# SmartThermo1_4.net
KiCad netlist of a schematic drawn in EAGLE
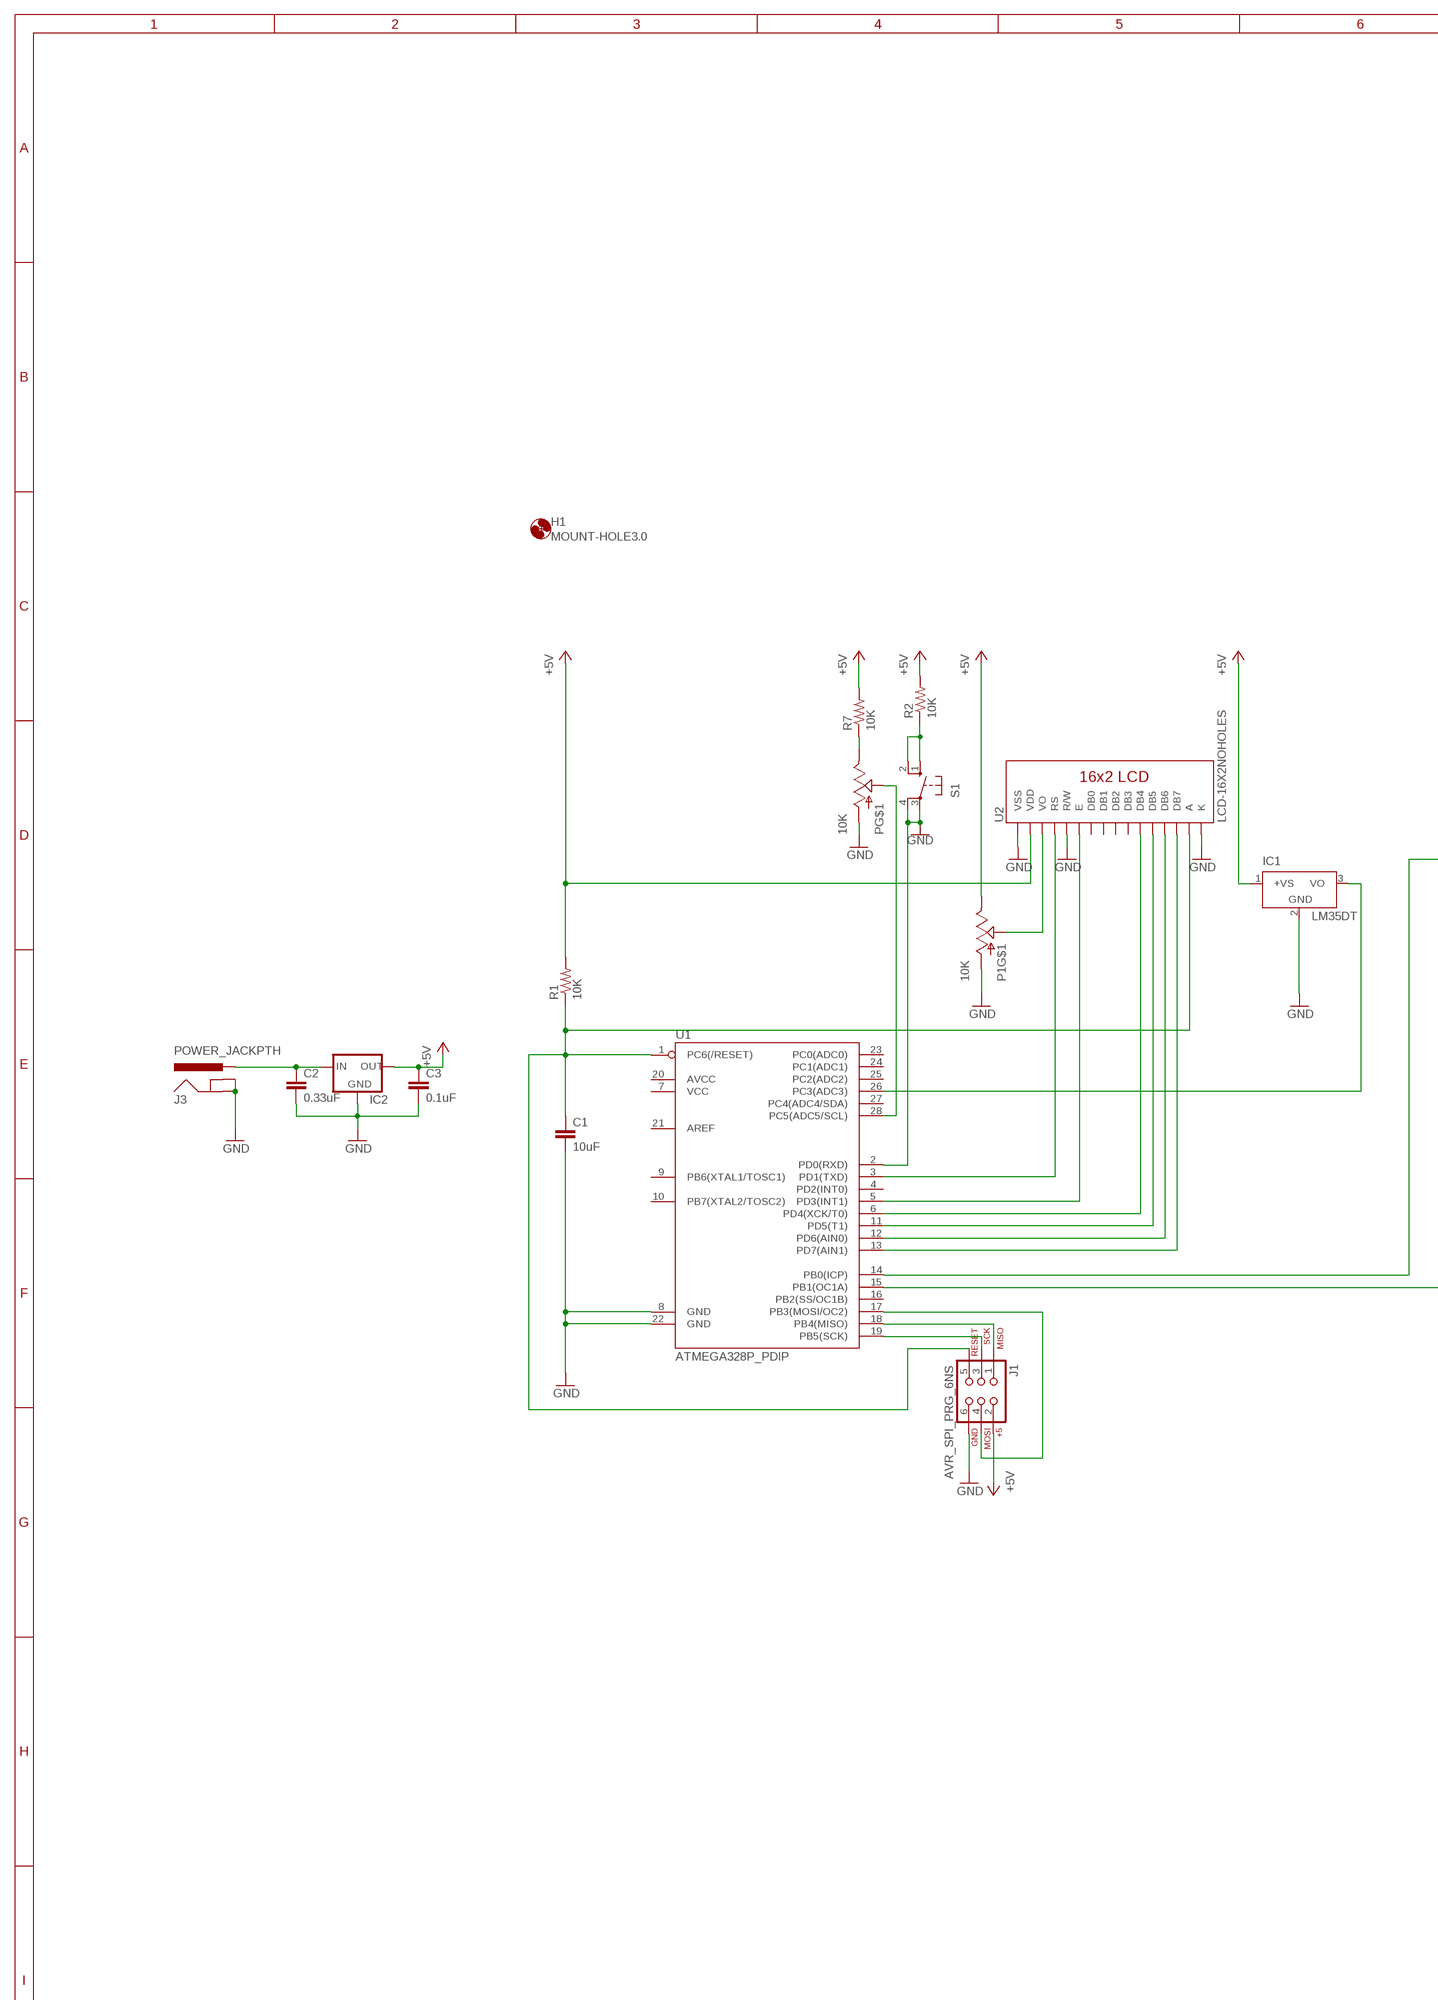
[diagram p0: schematic, sheet 1, part 1 of 2]
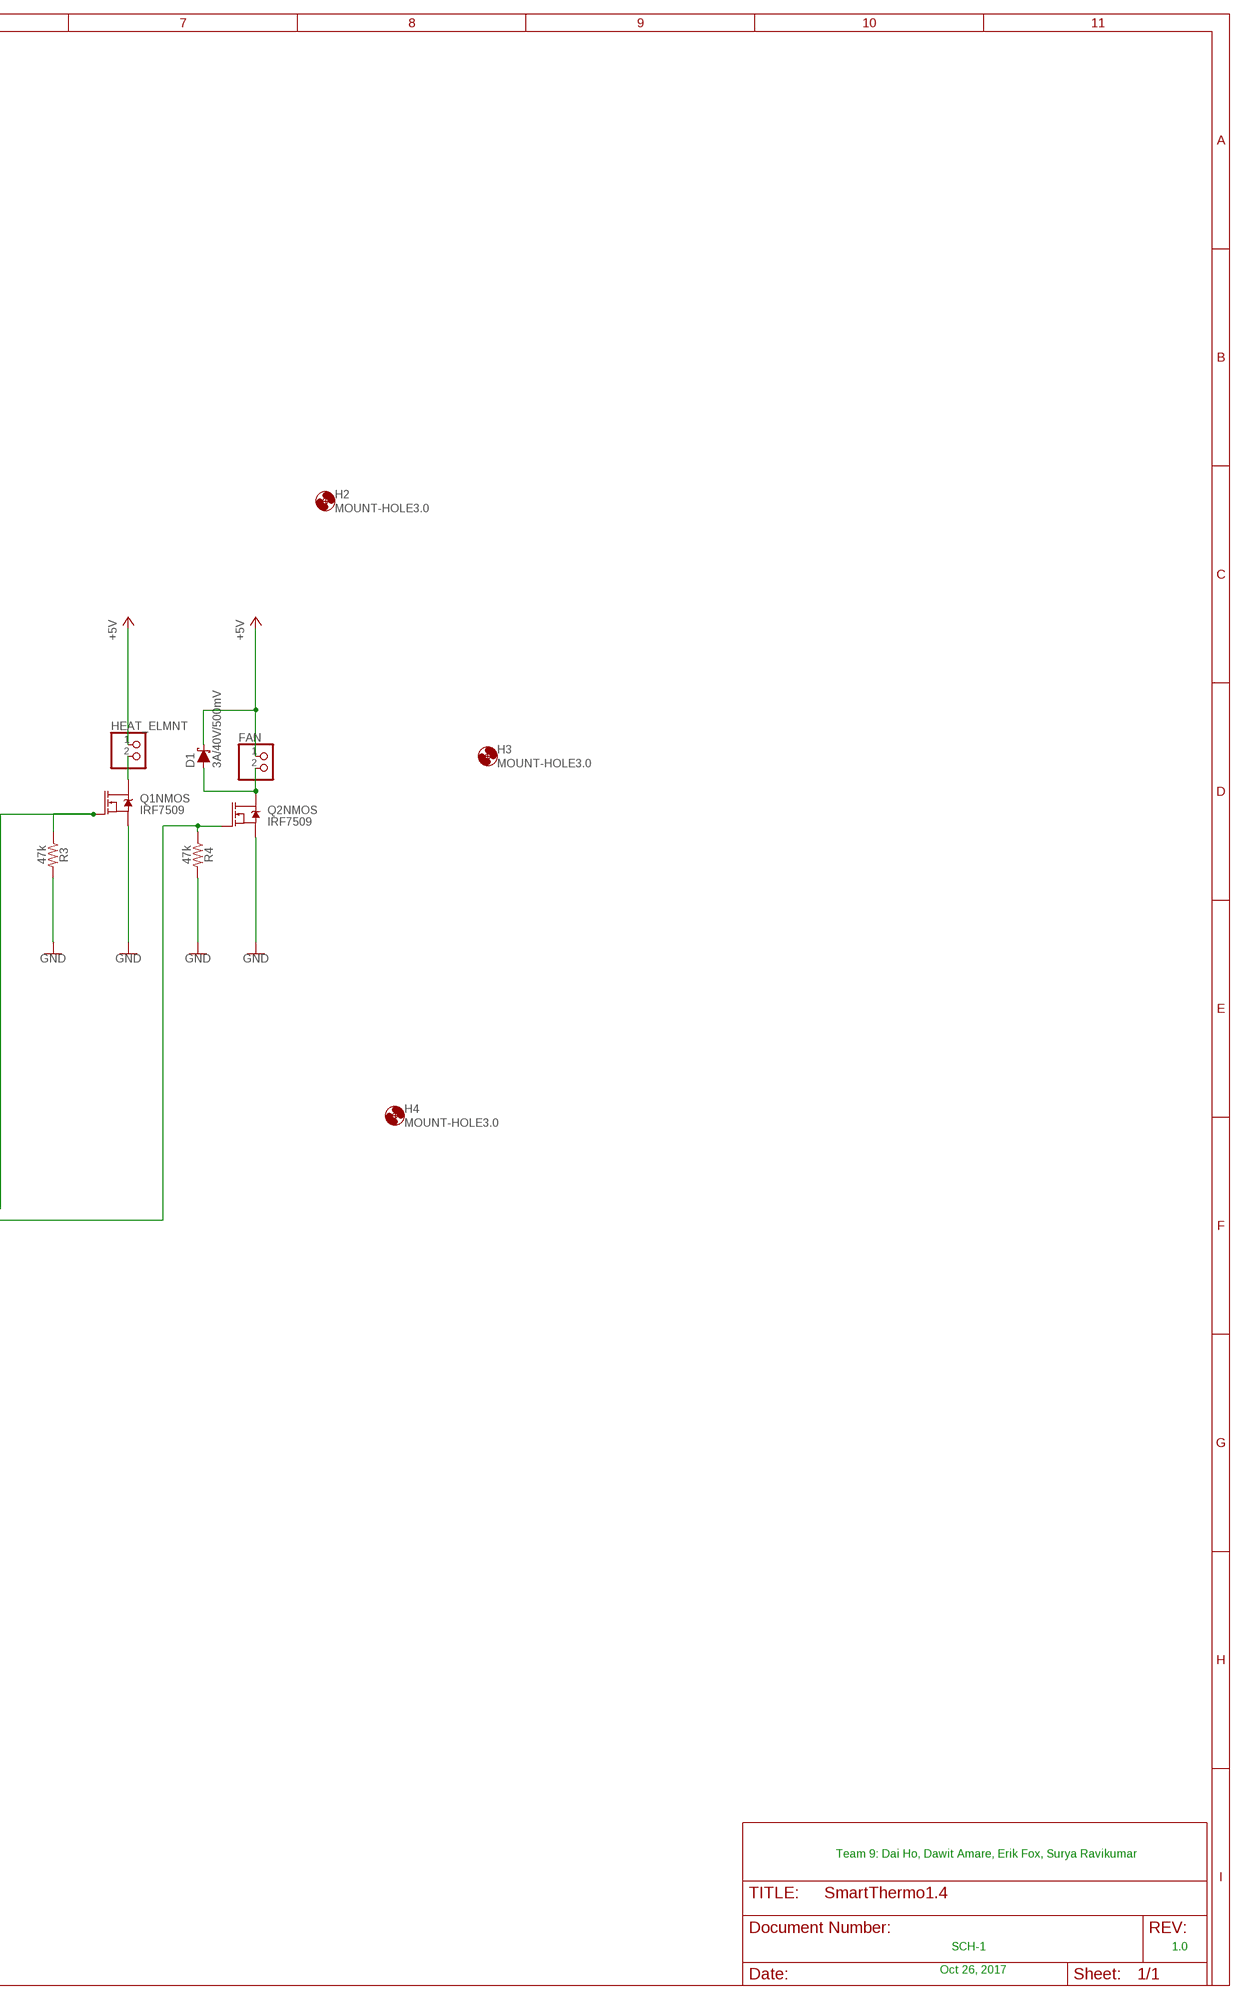
[diagram p1: schematic, sheet 1, part 2 of 2]

(export (version "E")
  (design (tool "Eeschema 10.0.6"))
  (components
    (comp (ref "C1")
      (value "10uF")
      (footprint "eagle-import:1206")
      (libsource (lib "eagle-import") (part "10UF-6.3V-20%(1206)"))
    )
    (comp (ref "C2")
      (value "0.33uF")
      (footprint "eagle-import:C7.5B3")
      (libsource (lib "eagle-import") (part "C7.5/3"))
    )
    (comp (ref "C3")
      (value "0.1uF")
      (footprint "eagle-import:C7.5B3")
      (libsource (lib "eagle-import") (part "C7.5/3"))
    )
    (comp (ref "D1")
      (value "3A/40V/500mV")
      (footprint "eagle-import:SMA-DIODE")
      (libsource (lib "eagle-import") (part "DIODE-SCHOTTKY-B340A"))
    )
    (comp (ref "FAN")
      (value "PINHD-1X2/90")
      (footprint "eagle-import:1X02_90")
      (libsource (lib "eagle-import") (part "PINHD-1X2/90"))
    )
    (comp (ref "H1")
      (value "MOUNT-HOLE3.0")
      (footprint "eagle-import:3,0")
      (libsource (lib "eagle-import") (part "MOUNT-HOLE3.0"))
    )
    (comp (ref "H2")
      (value "MOUNT-HOLE3.0")
      (footprint "eagle-import:3,0")
      (libsource (lib "eagle-import") (part "MOUNT-HOLE3.0"))
    )
    (comp (ref "H3")
      (value "MOUNT-HOLE3.0")
      (footprint "eagle-import:3,0")
      (libsource (lib "eagle-import") (part "MOUNT-HOLE3.0"))
    )
    (comp (ref "H4")
      (value "MOUNT-HOLE3.0")
      (footprint "eagle-import:3,0")
      (libsource (lib "eagle-import") (part "MOUNT-HOLE3.0"))
    )
    (comp (ref "HEAT_ELMNT")
      (value "PINHD-1X2/90")
      (footprint "eagle-import:1X02_90")
      (libsource (lib "eagle-import") (part "PINHD-1X2/90"))
    )
    (comp (ref "IC1")
      (value "LM35DT")
      (footprint "eagle-import:TO220V")
      (libsource (lib "eagle-import") (part "LM35DT"))
    )
    (comp (ref "IC2")
      (value "78XXL")
      (footprint "eagle-import:78XXL")
      (libsource (lib "eagle-import") (part "78XXL"))
    )
    (comp (ref "J1")
      (value "AVR_SPI_PRG_6NS")
      (footprint "eagle-import:2X3-NS")
      (libsource (lib "eagle-import") (part "AVR_SPI_PRG_6NS"))
    )
    (comp (ref "J3")
      (value "POWER_JACKPTH")
      (footprint "eagle-import:POWER_JACK_PTH")
      (libsource (lib "eagle-import") (part "POWER_JACKPTH"))
    )
    (comp (ref "P")
      (value "10K")
      (footprint "eagle-import:POT_PTH")
      (libsource (lib "eagle-import") (part "POT_SWITCHPOT_PTH"))
    )
    (comp (ref "P1")
      (value "10K")
      (footprint "eagle-import:POT_PTH")
      (libsource (lib "eagle-import") (part "POT_SWITCHPOT_PTH"))
    )
    (comp (ref "Q1")
      (value "IRF7509")
      (footprint "eagle-import:MSOP8")
      (libsource (lib "eagle-import") (part "IRF7509"))
    )
    (comp (ref "Q2")
      (value "IRF7509")
      (footprint "eagle-import:MSOP8")
      (libsource (lib "eagle-import") (part "IRF7509"))
    )
    (comp (ref "R1")
      (value "10K")
      (footprint "eagle-import:1206")
      (libsource (lib "eagle-import") (part "RESISTOR1206"))
    )
    (comp (ref "R2")
      (value "10K")
      (footprint "eagle-import:1206")
      (libsource (lib "eagle-import") (part "RESISTOR1206"))
    )
    (comp (ref "R3")
      (value "47k")
      (footprint "eagle-import:0603")
      (libsource (lib "eagle-import") (part "47KOHM-0603-1/10W-1%"))
    )
    (comp (ref "R4")
      (value "47k")
      (footprint "eagle-import:0603")
      (libsource (lib "eagle-import") (part "47KOHM-0603-1/10W-1%"))
    )
    (comp (ref "R7")
      (value "10K")
      (footprint "eagle-import:1206")
      (libsource (lib "eagle-import") (part "RESISTOR1206"))
    )
    (comp (ref "S1")
      (value "10-XX")
      (footprint "eagle-import:B3F-10XX")
      (fields (field (name "MPN") "B3F-1000"))
      (libsource (lib "eagle-import") (part "10-XX"))
    )
    (comp (ref "U1")
      (value "ATMEGA328P_PDIP")
      (footprint "eagle-import:DIL28-3")
      (libsource (lib "eagle-import") (part "ATMEGA328P_PDIP"))
    )
    (comp (ref "U2")
      (value "LCD-16X2NOHOLES")
      (footprint "eagle-import:LCD-16X2_NOHOLES")
      (libsource (lib "eagle-import") (part "LCD-16X2NOHOLES"))
    )
  )
  (nets
    (net (code "1") (name "+5V") (class "Default")
      (node (ref "C3") (pin "1") (pinfunction "1_1") (pintype "passive"))
      (node (ref "D1") (pin "C") (pinfunction "C_C") (pintype "passive"))
      (node (ref "FAN") (pin "1") (pinfunction "1_1") (pintype "passive"))
      (node (ref "HEAT_ELMNT") (pin "1") (pinfunction "1_1") (pintype "passive"))
      (node (ref "IC1") (pin "1") (pinfunction "+VS_1") (pintype "input"))
      (node (ref "IC2") (pin "OUT") (pinfunction "OUT_OUT") (pintype "passive"))
      (node (ref "J1") (pin "2") (pinfunction "2_2") (pintype "passive"))
      (node (ref "P1") (pin "E@2") (pinfunction "E_E@2") (pintype "passive"))
      (node (ref "R1") (pin "2") (pinfunction "2_2") (pintype "passive"))
      (node (ref "R2") (pin "2") (pinfunction "2_2") (pintype "passive"))
      (node (ref "R7") (pin "2") (pinfunction "2_2") (pintype "passive"))
      (node (ref "U2") (pin "2") (pinfunction "VDD_2") (pintype "power_in"))
    )
    (net (code "2") (name "GND") (class "Default")
      (node (ref "C1") (pin "2") (pinfunction "2_2") (pintype "passive"))
      (node (ref "C2") (pin "2") (pinfunction "2_2") (pintype "passive"))
      (node (ref "C3") (pin "2") (pinfunction "2_2") (pintype "passive"))
      (node (ref "IC1") (pin "2") (pinfunction "GND_2") (pintype "power_in"))
      (node (ref "IC2") (pin "GND") (pinfunction "GND_GND") (pintype "input"))
      (node (ref "J1") (pin "6") (pinfunction "6_6") (pintype "passive"))
      (node (ref "J3") (pin "GND") (pinfunction "GND_GND") (pintype "bidirectional"))
      (node (ref "J3") (pin "GNDBREAK") (pinfunction "GNDBREAK_GNDBREAK") (pintype "bidirectional"))
      (node (ref "P") (pin "E@1") (pinfunction "A_E@1") (pintype "passive"))
      (node (ref "P1") (pin "E@1") (pinfunction "A_E@1") (pintype "passive"))
      (node (ref "Q1") (pin "1") (pinfunction "S_1") (pintype "bidirectional"))
      (node (ref "Q2") (pin "1") (pinfunction "S_1") (pintype "bidirectional"))
      (node (ref "R3") (pin "2") (pinfunction "2_2") (pintype "passive"))
      (node (ref "R4") (pin "2") (pinfunction "2_2") (pintype "passive"))
      (node (ref "S1") (pin "3") (pinfunction "P_3") (pintype "passive"))
      (node (ref "S1") (pin "4") (pinfunction "P1_4") (pintype "passive"))
      (node (ref "U1") (pin "2") (pinfunction "PD0(RXD)_2") (pintype "bidirectional"))
      (node (ref "U1") (pin "22") (pinfunction "GND_22") (pintype "bidirectional"))
      (node (ref "U1") (pin "8") (pinfunction "GND_8") (pintype "bidirectional"))
      (node (ref "U2") (pin "1") (pinfunction "VSS_1") (pintype "power_in"))
      (node (ref "U2") (pin "16") (pinfunction "K_16") (pintype "power_in"))
      (node (ref "U2") (pin "5") (pinfunction "R/W_5") (pintype "input"))
    )
    (net (code "3") (name "Net-(C2-Pad1)") (class "Default")
      (node (ref "C2") (pin "1") (pinfunction "1_1") (pintype "passive"))
      (node (ref "IC2") (pin "IN") (pinfunction "IN_IN") (pintype "input"))
      (node (ref "J3") (pin "PWR") (pinfunction "PWR_PWR") (pintype "bidirectional"))
    )
    (net (code "4") (name "Net-(D1-PadA)") (class "Default")
      (node (ref "D1") (pin "A") (pinfunction "A_A") (pintype "passive"))
      (node (ref "FAN") (pin "2") (pinfunction "2_2") (pintype "passive"))
      (node (ref "Q2") (pin "7") (pinfunction "D_7") (pintype "bidirectional"))
      (node (ref "Q2") (pin "8") (pinfunction "D_8") (pintype "bidirectional"))
    )
    (net (code "5") (name "Net-(HEAT_ELMNT-Pad2)") (class "Default")
      (node (ref "HEAT_ELMNT") (pin "2") (pinfunction "2_2") (pintype "passive"))
      (node (ref "Q1") (pin "7") (pinfunction "D_7") (pintype "bidirectional"))
      (node (ref "Q1") (pin "8") (pinfunction "D_8") (pintype "bidirectional"))
    )
    (net (code "6") (name "Net-(IC1-VO)") (class "Default")
      (node (ref "IC1") (pin "3") (pinfunction "VO_3") (pintype "input"))
      (node (ref "U1") (pin "26") (pinfunction "PC3(ADC3)_26") (pintype "bidirectional"))
    )
    (net (code "7") (name "Net-(P1A-S)") (class "Default")
      (node (ref "P1") (pin "WAND") (pinfunction "S_WAND") (pintype "passive"))
      (node (ref "U2") (pin "3") (pinfunction "VO_3") (pintype "bidirectional"))
    )
    (net (code "8") (name "Net-(PA-E)") (class "Default")
      (node (ref "P") (pin "E@2") (pinfunction "E_E@2") (pintype "passive"))
      (node (ref "R7") (pin "1") (pinfunction "1_1") (pintype "passive"))
    )
    (net (code "9") (name "Net-(PA-S)") (class "Default")
      (node (ref "P") (pin "WAND") (pinfunction "S_WAND") (pintype "passive"))
      (node (ref "U1") (pin "28") (pinfunction "PC5(ADC5/SCL)_28") (pintype "bidirectional"))
    )
    (net (code "10") (name "Net-(Q1A-G)") (class "Default")
      (node (ref "Q1") (pin "2") (pinfunction "G_2") (pintype "bidirectional"))
      (node (ref "R3") (pin "1") (pinfunction "1_1") (pintype "passive"))
      (node (ref "U1") (pin "14") (pinfunction "PB0(ICP)_14") (pintype "bidirectional"))
    )
    (net (code "11") (name "Net-(Q2A-G)") (class "Default")
      (node (ref "Q2") (pin "2") (pinfunction "G_2") (pintype "bidirectional"))
      (node (ref "R4") (pin "1") (pinfunction "1_1") (pintype "passive"))
      (node (ref "U1") (pin "15") (pinfunction "PB1(OC1A)_15") (pintype "bidirectional"))
    )
    (net (code "12") (name "Net-(S1-S)") (class "Default")
      (node (ref "R2") (pin "1") (pinfunction "1_1") (pintype "passive"))
      (node (ref "S1") (pin "1") (pinfunction "S_1") (pintype "passive"))
      (node (ref "S1") (pin "2") (pinfunction "S1_2") (pintype "passive"))
    )
    (net (code "13") (name "Net-(U1-PB3(MOSI{slash}OC2))") (class "Default")
      (node (ref "J1") (pin "4") (pinfunction "4_4") (pintype "passive"))
      (node (ref "U1") (pin "17") (pinfunction "PB3(MOSI/OC2)_17") (pintype "bidirectional"))
    )
    (net (code "14") (name "Net-(U1-PB4(MISO))") (class "Default")
      (node (ref "J1") (pin "1") (pinfunction "1_1") (pintype "passive"))
      (node (ref "U1") (pin "18") (pinfunction "PB4(MISO)_18") (pintype "bidirectional"))
    )
    (net (code "15") (name "Net-(U1-PB5(SCK))") (class "Default")
      (node (ref "J1") (pin "3") (pinfunction "3_3") (pintype "passive"))
      (node (ref "U1") (pin "19") (pinfunction "PB5(SCK)_19") (pintype "bidirectional"))
    )
    (net (code "16") (name "Net-(U1-PC6({slash}RESET))") (class "Default")
      (node (ref "C1") (pin "1") (pinfunction "1_1") (pintype "passive"))
      (node (ref "J1") (pin "5") (pinfunction "5_5") (pintype "passive"))
      (node (ref "R1") (pin "1") (pinfunction "1_1") (pintype "passive"))
      (node (ref "U1") (pin "1") (pinfunction "PC6(/RESET)_1") (pintype "bidirectional"))
      (node (ref "U2") (pin "15") (pinfunction "A_15") (pintype "power_in"))
    )
    (net (code "17") (name "Net-(U1-PD1(TXD))") (class "Default")
      (node (ref "U1") (pin "3") (pinfunction "PD1(TXD)_3") (pintype "bidirectional"))
      (node (ref "U2") (pin "4") (pinfunction "RS_4") (pintype "input"))
    )
    (net (code "18") (name "Net-(U1-PD3(INT1))") (class "Default")
      (node (ref "U1") (pin "5") (pinfunction "PD3(INT1)_5") (pintype "bidirectional"))
      (node (ref "U2") (pin "6") (pinfunction "E_6") (pintype "input"))
    )
    (net (code "19") (name "Net-(U1-PD4(XCK{slash}T0))") (class "Default")
      (node (ref "U1") (pin "6") (pinfunction "PD4(XCK/T0)_6") (pintype "bidirectional"))
      (node (ref "U2") (pin "11") (pinfunction "DB4_11") (pintype "bidirectional"))
    )
    (net (code "20") (name "Net-(U1-PD5(T1))") (class "Default")
      (node (ref "U1") (pin "11") (pinfunction "PD5(T1)_11") (pintype "bidirectional"))
      (node (ref "U2") (pin "12") (pinfunction "DB5_12") (pintype "bidirectional"))
    )
    (net (code "21") (name "Net-(U1-PD6(AIN0))") (class "Default")
      (node (ref "U1") (pin "12") (pinfunction "PD6(AIN0)_12") (pintype "bidirectional"))
      (node (ref "U2") (pin "13") (pinfunction "DB6_13") (pintype "bidirectional"))
    )
    (net (code "22") (name "Net-(U1-PD7(AIN1))") (class "Default")
      (node (ref "U1") (pin "13") (pinfunction "PD7(AIN1)_13") (pintype "bidirectional"))
      (node (ref "U2") (pin "14") (pinfunction "DB7_14") (pintype "bidirectional"))
    )
    (net (code "23") (name "unconnected-(U1-AREF-Pad21)") (class "Default")
      (node (ref "U1") (pin "21") (pinfunction "AREF_21") (pintype "bidirectional"))
    )
    (net (code "24") (name "unconnected-(U1-AVCC-Pad20)") (class "Default")
      (node (ref "U1") (pin "20") (pinfunction "AVCC_20") (pintype "bidirectional"))
    )
    (net (code "25") (name "unconnected-(U1-PB2(SS{slash}OC1B)-Pad16)") (class "Default")
      (node (ref "U1") (pin "16") (pinfunction "PB2(SS/OC1B)_16") (pintype "bidirectional"))
    )
    (net (code "26") (name "unconnected-(U1-PB6(XTAL1{slash}TOSC1)-Pad9)") (class "Default")
      (node (ref "U1") (pin "9") (pinfunction "PB6(XTAL1/TOSC1)_9") (pintype "bidirectional"))
    )
    (net (code "27") (name "unconnected-(U1-PB7(XTAL2{slash}TOSC2)-Pad10)") (class "Default")
      (node (ref "U1") (pin "10") (pinfunction "PB7(XTAL2/TOSC2)_10") (pintype "bidirectional"))
    )
    (net (code "28") (name "unconnected-(U1-PC0(ADC0)-Pad23)") (class "Default")
      (node (ref "U1") (pin "23") (pinfunction "PC0(ADC0)_23") (pintype "bidirectional"))
    )
    (net (code "29") (name "unconnected-(U1-PC1(ADC1)-Pad24)") (class "Default")
      (node (ref "U1") (pin "24") (pinfunction "PC1(ADC1)_24") (pintype "bidirectional"))
    )
    (net (code "30") (name "unconnected-(U1-PC2(ADC2)-Pad25)") (class "Default")
      (node (ref "U1") (pin "25") (pinfunction "PC2(ADC2)_25") (pintype "bidirectional"))
    )
    (net (code "31") (name "unconnected-(U1-PC4(ADC4{slash}SDA)-Pad27)") (class "Default")
      (node (ref "U1") (pin "27") (pinfunction "PC4(ADC4/SDA)_27") (pintype "bidirectional"))
    )
    (net (code "32") (name "unconnected-(U1-PD2(INT0)-Pad4)") (class "Default")
      (node (ref "U1") (pin "4") (pinfunction "PD2(INT0)_4") (pintype "bidirectional"))
    )
    (net (code "33") (name "unconnected-(U1-VCC-Pad7)") (class "Default")
      (node (ref "U1") (pin "7") (pinfunction "VCC_7") (pintype "bidirectional"))
    )
    (net (code "34") (name "unconnected-(U2-DB0-Pad7)") (class "Default")
      (node (ref "U2") (pin "7") (pinfunction "DB0_7") (pintype "bidirectional"))
    )
    (net (code "35") (name "unconnected-(U2-DB1-Pad8)") (class "Default")
      (node (ref "U2") (pin "8") (pinfunction "DB1_8") (pintype "bidirectional"))
    )
    (net (code "36") (name "unconnected-(U2-DB2-Pad9)") (class "Default")
      (node (ref "U2") (pin "9") (pinfunction "DB2_9") (pintype "bidirectional"))
    )
    (net (code "37") (name "unconnected-(U2-DB3-Pad10)") (class "Default")
      (node (ref "U2") (pin "10") (pinfunction "DB3_10") (pintype "bidirectional"))
    )
  )
)
